# CONTROL_BOARD_V2.net
KiCad netlist of a schematic drawn in Altium Designer
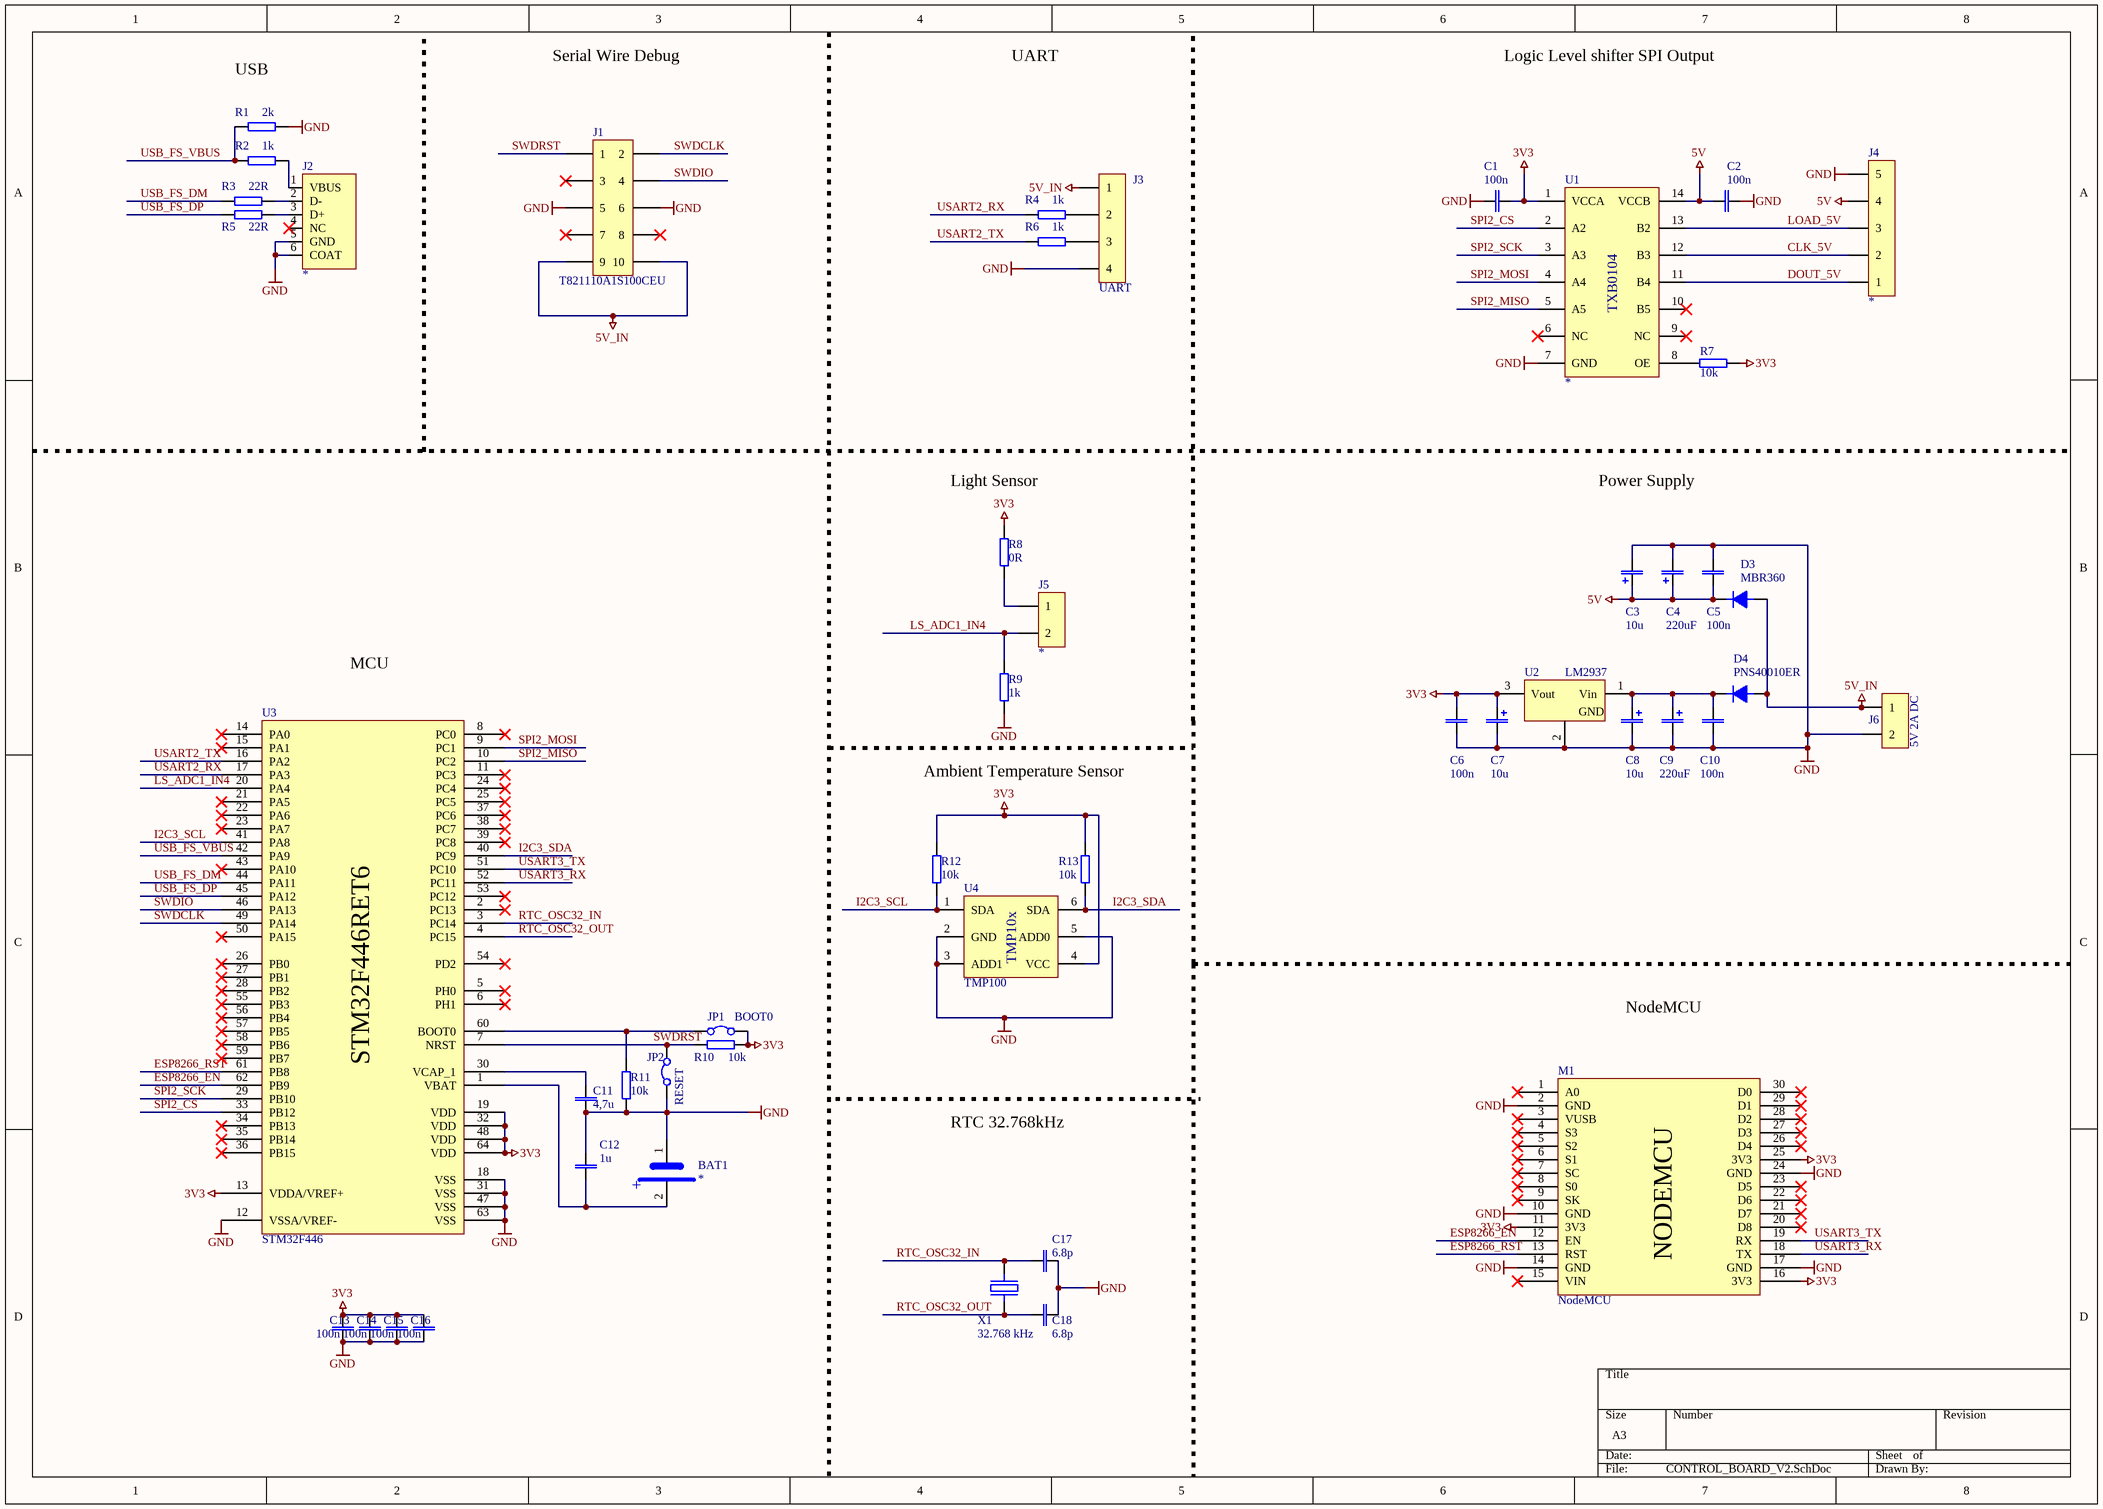
[diagram p0: CONTROL_BOARD_V2.SchDoc]

(export (version "E")
  (design (tool "Eeschema 10.0.6"))
  (components
    (comp (ref "BAT1")
      (value "*")
      (footprint "CR2032")
      (description "battery")
      (libsource (lib "SCH_LIB") (part "Battery"))
    )
    (comp (ref "C1")
      (value "100n")
      (footprint "CAP 0805")
      (description "NON POLARIZED CAPACITOR")
      (libsource (lib "SCH_LIB") (part "CAP"))
    )
    (comp (ref "C2")
      (value "100n")
      (footprint "CAP 0805")
      (description "NON POLARIZED CAPACITOR")
      (libsource (lib "SCH_LIB") (part "CAP"))
    )
    (comp (ref "C3")
      (value "10u")
      (footprint "CAP 1210")
      (description "POLARIZED CAPACITOR")
      (libsource (lib "SCH_LIB") (part "CAP_POL"))
    )
    (comp (ref "C4")
      (value "220uF")
      (footprint "G ELKO")
      (description "POLARIZED CAPACITOR")
      (libsource (lib "SCH_LIB") (part "CAP_POL"))
    )
    (comp (ref "C5")
      (value "100n")
      (footprint "CAP 0805")
      (description "NON POLARIZED CAPACITOR")
      (libsource (lib "SCH_LIB") (part "CAP"))
    )
    (comp (ref "C6")
      (value "100n")
      (footprint "CAP 0805")
      (description "NON POLARIZED CAPACITOR")
      (libsource (lib "SCH_LIB") (part "CAP"))
    )
    (comp (ref "C7")
      (value "10u")
      (footprint "CAP 1210")
      (description "POLARIZED CAPACITOR")
      (libsource (lib "SCH_LIB") (part "CAP_POL"))
    )
    (comp (ref "C8")
      (value "10u")
      (footprint "CAP 1210")
      (description "POLARIZED CAPACITOR")
      (libsource (lib "SCH_LIB") (part "CAP_POL"))
    )
    (comp (ref "C9")
      (value "220uF")
      (footprint "G ELKO")
      (description "POLARIZED CAPACITOR")
      (libsource (lib "SCH_LIB") (part "CAP_POL"))
    )
    (comp (ref "C10")
      (value "100n")
      (footprint "CAP 0805")
      (description "NON POLARIZED CAPACITOR")
      (libsource (lib "SCH_LIB") (part "CAP"))
    )
    (comp (ref "C11")
      (value "4,7u")
      (footprint "CAP 0805")
      (description "NON POLARIZED CAPACITOR")
      (libsource (lib "SCH_LIB") (part "CAP"))
    )
    (comp (ref "C12")
      (value "1u")
      (footprint "CAP 0805")
      (description "NON POLARIZED CAPACITOR")
      (libsource (lib "SCH_LIB") (part "CAP"))
    )
    (comp (ref "C13")
      (value "100n")
      (footprint "CAP 0805")
      (description "NON POLARIZED CAPACITOR")
      (libsource (lib "SCH_LIB") (part "CAP"))
    )
    (comp (ref "C14")
      (value "100n")
      (footprint "CAP 0805")
      (description "NON POLARIZED CAPACITOR")
      (libsource (lib "SCH_LIB") (part "CAP"))
    )
    (comp (ref "C15")
      (value "100n")
      (footprint "CAP 0805")
      (description "NON POLARIZED CAPACITOR")
      (libsource (lib "SCH_LIB") (part "CAP"))
    )
    (comp (ref "C16")
      (value "100n")
      (footprint "CAP 0805")
      (description "NON POLARIZED CAPACITOR")
      (libsource (lib "SCH_LIB") (part "CAP"))
    )
    (comp (ref "C17")
      (value "6.8p")
      (footprint "CAP 0805")
      (description "NON POLARIZED CAPACITOR")
      (libsource (lib "SCH_LIB") (part "CAP"))
    )
    (comp (ref "C18")
      (value "6.8p")
      (footprint "CAP 0805")
      (description "NON POLARIZED CAPACITOR")
      (libsource (lib "SCH_LIB") (part "CAP"))
    )
    (comp (ref "D3")
      (value "MBR360")
      (footprint "DO-201AD")
      (description "ON Semiconductor MBR360,SCHOTTKY BARRIER RECTIFIERS\r\n3.0 AMPERES 60 VOLTS")
      (fields (field (name "MANUFACTURER") "ON Semiconductor"))
      (libsource (lib "SCH_LIB") (part "MBR360"))
    )
    (comp (ref "D4")
      (value "PNS40010ER")
      (footprint "SOD-123")
      (description "Nexperia PNS40010ER,115 switching diode 1.4A, 400V, SOD-123")
      (fields (field (name "MANUFACTURER") "Nexperia"))
      (libsource (lib "SCH_LIB") (part "PNS40010ER"))
    )
    (comp (ref "J1")
      (value "T821110A1S100CEU")
      (footprint "MLW10")
      (description "T821, 10pin, 2x5 connector, 2.54mm")
      (fields (field (name "MANUFACTURER") "Amphenol"))
      (libsource (lib "SCH_LIB") (part "T821-10"))
    )
    (comp (ref "J2")
      (value "*")
      (footprint "MUSB-B2.0S05PFHSB-T")
      (description "5PIN miniUSB SMD connector")
      (libsource (lib "SCH_LIB") (part "USB_5PIN"))
    )
    (comp (ref "J3")
      (value "UART")
      (footprint "SIL4")
      (description "4 PIN HEADER")
      (libsource (lib "SCH_LIB") (part "HEADER4"))
    )
    (comp (ref "J4")
      (value "*")
      (footprint "SIL5")
      (description "5 PIN HEADER")
      (libsource (lib "SCH_LIB") (part "HEADER5"))
    )
    (comp (ref "J5")
      (value "*")
      (footprint "SIL2")
      (description "2 PIN HEADER")
      (libsource (lib "SCH_LIB") (part "HEADER2"))
    )
    (comp (ref "J6")
      (value "5V 2A DC")
      (footprint "PTR_AKZ350")
      (description "2 Pin Terminal Block")
      (fields (field (name "MANUFACTURER") "TE Connectivity"))
      (libsource (lib "SCH_LIB") (part "TB-2"))
    )
    (comp (ref "JP1")
      (value "BOOT0")
      (footprint "SIL2")
      (description "JUMPER")
      (libsource (lib "SCH_LIB") (part "JUMPER"))
    )
    (comp (ref "JP2")
      (value "RESET")
      (footprint "SIL2")
      (description "JUMPER")
      (libsource (lib "SCH_LIB") (part "JUMPER"))
    )
    (comp (ref "M1")
      (value "NodeMCU")
      (footprint "NodeMcu")
      (description "Node MCU ESP12 module")
      (libsource (lib "SCH_LIB") (part "NodeMCU"))
    )
    (comp (ref "R1")
      (value "2k")
      (footprint "RES 0805")
      (description "RESISTOR")
      (libsource (lib "SCH_LIB") (part "RES"))
    )
    (comp (ref "R2")
      (value "1k")
      (footprint "RES 0805")
      (description "RESISTOR")
      (libsource (lib "SCH_LIB") (part "RES"))
    )
    (comp (ref "R3")
      (value "22R")
      (footprint "RES 0805")
      (description "RESISTOR")
      (libsource (lib "SCH_LIB") (part "RES"))
    )
    (comp (ref "R4")
      (value "1k")
      (footprint "RES 0805")
      (description "RESISTOR")
      (libsource (lib "SCH_LIB") (part "RES"))
    )
    (comp (ref "R5")
      (value "22R")
      (footprint "RES 0805")
      (description "RESISTOR")
      (libsource (lib "SCH_LIB") (part "RES"))
    )
    (comp (ref "R6")
      (value "1k")
      (footprint "RES 0805")
      (description "RESISTOR")
      (libsource (lib "SCH_LIB") (part "RES"))
    )
    (comp (ref "R7")
      (value "10k")
      (footprint "RES 0805")
      (description "RESISTOR")
      (libsource (lib "SCH_LIB") (part "RES"))
    )
    (comp (ref "R8")
      (value "0R")
      (footprint "RES 0805")
      (description "RESISTOR")
      (libsource (lib "") (part "RES_2"))
    )
    (comp (ref "R9")
      (value "1k")
      (footprint "RES 0805")
      (description "RESISTOR")
      (libsource (lib "") (part "RES_2"))
    )
    (comp (ref "R10")
      (value "10k")
      (footprint "RES 0805")
      (description "RESISTOR")
      (libsource (lib "") (part "RES_3"))
    )
    (comp (ref "R11")
      (value "10k")
      (footprint "RES 0805")
      (description "RESISTOR")
      (libsource (lib "") (part "RES_1"))
    )
    (comp (ref "R12")
      (value "10k")
      (footprint "RES 0805")
      (description "RESISTOR")
      (libsource (lib "") (part "RES_1"))
    )
    (comp (ref "R13")
      (value "10k")
      (footprint "RES 0805")
      (description "RESISTOR")
      (libsource (lib "") (part "RES_1"))
    )
    (comp (ref "U1")
      (value "*")
      (footprint "SO14")
      (description "Voltage level shifter")
      (libsource (lib "SCH_LIB") (part "TXB0104"))
    )
    (comp (ref "U2")
      (value "LM2937")
      (footprint "SOT223")
      (description "LDO-regulator 400mA 3,3 V 5%, 4,75 → 26 V, SOT223")
      (fields (field (name "MANUFACTURER") "Texas Instruments"))
      (libsource (lib "SCH_LIB") (part "LM2937"))
    )
    (comp (ref "U3")
      (value "STM32F446")
      (footprint "LQFP64")
      (description "MCU STM32F446RET6 32bit, ARM Cortex M4, 180MHz, Flash, 128 kB RAM, 2xUSB USB, LQFP-64")
      (fields (field (name "MANUFACTURER") "ST Microelectronics"))
      (libsource (lib "SCH_LIB") (part "STM32F446RET6"))
    )
    (comp (ref "U4")
      (value "TMP100")
      (footprint "SOT-23-6L")
      (description "Temperature sensor with I2C interface")
      (fields (field (name "MANUFACTURER") "Texas Instruments"))
      (libsource (lib "SCH_LIB") (part "TMP10x"))
    )
    (comp (ref "X1")
      (value "32.768 kHz")
      (footprint "X32K768L104")
      (description "Crystal, 32.768 kHz, Cylinder Radial, 8mm x 3mm Dia, 12.5 pF, 20 ppm")
      (fields (field (name "MANUFACTURER") "AEL CRYSTALS"))
      (libsource (lib "SCH_LIB") (part "X32K768L104"))
    )
  )
  (nets
    (net (code "1") (name "/CLK_5V") (class "Default")
      (node (ref "J4") (pin "2") (pinfunction "2_2") (pintype "passive"))
      (node (ref "U1") (pin "12") (pinfunction "B3_12") (pintype "passive"))
    )
    (net (code "2") (name "/DOUT_5V") (class "Default")
      (node (ref "J4") (pin "1") (pinfunction "1_1") (pintype "passive"))
      (node (ref "U1") (pin "11") (pinfunction "B4_11") (pintype "passive"))
    )
    (net (code "3") (name "/ESP8266_EN") (class "Default")
      (node (ref "M1") (pin "12") (pinfunction "EN_12") (pintype "passive"))
      (node (ref "U3") (pin "62") (pinfunction "PB9_62") (pintype "passive"))
    )
    (net (code "4") (name "/ESP8266_RST") (class "Default")
      (node (ref "M1") (pin "13") (pinfunction "RST_13") (pintype "passive"))
      (node (ref "U3") (pin "61") (pinfunction "PB8_61") (pintype "passive"))
    )
    (net (code "5") (name "/I2C3_SCL") (class "Default")
      (node (ref "R12") (pin "1") (pinfunction "1_1") (pintype "passive"))
      (node (ref "U3") (pin "41") (pinfunction "PA8_41") (pintype "passive"))
      (node (ref "U4") (pin "1") (pinfunction "SDA_1") (pintype "passive"))
    )
    (net (code "6") (name "/I2C3_SDA") (class "Default")
      (node (ref "R13") (pin "1") (pinfunction "1_1") (pintype "passive"))
      (node (ref "U3") (pin "40") (pinfunction "PC9_40") (pintype "passive"))
      (node (ref "U4") (pin "6") (pinfunction "SDA_6") (pintype "passive"))
    )
    (net (code "7") (name "/LOAD_5V") (class "Default")
      (node (ref "J4") (pin "3") (pinfunction "3_3") (pintype "passive"))
      (node (ref "U1") (pin "13") (pinfunction "B2_13") (pintype "passive"))
    )
    (net (code "8") (name "/LS_ADC1_IN4") (class "Default")
      (node (ref "J5") (pin "2") (pinfunction "2_2") (pintype "passive"))
      (node (ref "R9") (pin "1") (pinfunction "1_1") (pintype "passive"))
      (node (ref "U3") (pin "20") (pinfunction "PA4_20") (pintype "passive"))
    )
    (net (code "9") (name "/RTC_OSC32_IN") (class "Default")
      (node (ref "C17") (pin "2") (pinfunction "2_2") (pintype "passive"))
      (node (ref "U3") (pin "3") (pinfunction "PC14_3") (pintype "passive"))
      (node (ref "X1") (pin "2") (pinfunction "GND_2") (pintype "passive"))
    )
    (net (code "10") (name "/RTC_OSC32_OUT") (class "Default")
      (node (ref "C18") (pin "2") (pinfunction "2_2") (pintype "passive"))
      (node (ref "U3") (pin "4") (pinfunction "PC15_4") (pintype "passive"))
      (node (ref "X1") (pin "1") (pinfunction "1_1") (pintype "passive"))
    )
    (net (code "11") (name "/SPI2_CS") (class "Default")
      (node (ref "U1") (pin "2") (pinfunction "A2_2") (pintype "passive"))
      (node (ref "U3") (pin "33") (pinfunction "PB12_33") (pintype "passive"))
    )
    (net (code "12") (name "/SPI2_MISO") (class "Default")
      (node (ref "U1") (pin "5") (pinfunction "A5_5") (pintype "passive"))
      (node (ref "U3") (pin "10") (pinfunction "PC2_10") (pintype "passive"))
    )
    (net (code "13") (name "/SPI2_MOSI") (class "Default")
      (node (ref "U1") (pin "4") (pinfunction "A4_4") (pintype "passive"))
      (node (ref "U3") (pin "9") (pinfunction "PC1_9") (pintype "passive"))
    )
    (net (code "14") (name "/SPI2_SCK") (class "Default")
      (node (ref "U1") (pin "3") (pinfunction "A3_3") (pintype "passive"))
      (node (ref "U3") (pin "29") (pinfunction "PB10_29") (pintype "passive"))
    )
    (net (code "15") (name "/SWDCLK") (class "Default")
      (node (ref "J1") (pin "2") (pinfunction "2_2") (pintype "passive"))
      (node (ref "U3") (pin "49") (pinfunction "PA14_49") (pintype "passive"))
    )
    (net (code "16") (name "/SWDIO") (class "Default")
      (node (ref "J1") (pin "4") (pinfunction "4_4") (pintype "passive"))
      (node (ref "U3") (pin "46") (pinfunction "PA13_46") (pintype "passive"))
    )
    (net (code "17") (name "/SWDRST") (class "Default")
      (node (ref "J1") (pin "1") (pinfunction "1_1") (pintype "passive"))
      (node (ref "JP2") (pin "2") (pinfunction "2_2") (pintype "passive"))
      (node (ref "R10") (pin "1") (pinfunction "1_1") (pintype "passive"))
      (node (ref "U3") (pin "7") (pinfunction "NRST_7") (pintype "passive"))
    )
    (net (code "18") (name "/USART2_RX") (class "Default")
      (node (ref "R4") (pin "2") (pinfunction "2_2") (pintype "passive"))
      (node (ref "U3") (pin "17") (pinfunction "PA3_17") (pintype "passive"))
    )
    (net (code "19") (name "/USART2_TX") (class "Default")
      (node (ref "R6") (pin "2") (pinfunction "2_2") (pintype "passive"))
      (node (ref "U3") (pin "16") (pinfunction "PA2_16") (pintype "passive"))
    )
    (net (code "20") (name "/USART3_RX") (class "Default")
      (node (ref "M1") (pin "18") (pinfunction "TX_18") (pintype "passive"))
      (node (ref "U3") (pin "52") (pinfunction "PC11_52") (pintype "passive"))
    )
    (net (code "21") (name "/USART3_TX") (class "Default")
      (node (ref "M1") (pin "19") (pinfunction "RX_19") (pintype "passive"))
      (node (ref "U3") (pin "51") (pinfunction "PC10_51") (pintype "passive"))
    )
    (net (code "22") (name "/USB_FS_DM") (class "Default")
      (node (ref "R3") (pin "2") (pinfunction "2_2") (pintype "passive"))
      (node (ref "U3") (pin "44") (pinfunction "PA11_44") (pintype "passive"))
    )
    (net (code "23") (name "/USB_FS_DP") (class "Default")
      (node (ref "R5") (pin "2") (pinfunction "2_2") (pintype "passive"))
      (node (ref "U3") (pin "45") (pinfunction "PA12_45") (pintype "passive"))
    )
    (net (code "24") (name "/USB_FS_VBUS") (class "Default")
      (node (ref "R1") (pin "2") (pinfunction "2_2") (pintype "passive"))
      (node (ref "R2") (pin "2") (pinfunction "2_2") (pintype "passive"))
      (node (ref "U3") (pin "42") (pinfunction "PA9_42") (pintype "passive"))
    )
    (net (code "25") (name "3V3") (class "Default")
      (node (ref "C1") (pin "2") (pinfunction "2_2") (pintype "passive"))
      (node (ref "C13") (pin "2") (pinfunction "2_2") (pintype "passive"))
      (node (ref "C14") (pin "2") (pinfunction "2_2") (pintype "passive"))
      (node (ref "C15") (pin "2") (pinfunction "2_2") (pintype "passive"))
      (node (ref "C16") (pin "2") (pinfunction "2_2") (pintype "passive"))
      (node (ref "C6") (pin "1") (pinfunction "1_1") (pintype "passive"))
      (node (ref "C7") (pin "1") (pinfunction "+_1") (pintype "passive"))
      (node (ref "JP1") (pin "2") (pinfunction "2_2") (pintype "passive"))
      (node (ref "M1") (pin "11") (pinfunction "3V3_11") (pintype "passive"))
      (node (ref "M1") (pin "16") (pinfunction "3V3_16") (pintype "passive"))
      (node (ref "M1") (pin "25") (pinfunction "3V3_25") (pintype "passive"))
      (node (ref "R10") (pin "2") (pinfunction "2_2") (pintype "passive"))
      (node (ref "R12") (pin "2") (pinfunction "2_2") (pintype "passive"))
      (node (ref "R13") (pin "2") (pinfunction "2_2") (pintype "passive"))
      (node (ref "R7") (pin "1") (pinfunction "1_1") (pintype "passive"))
      (node (ref "R8") (pin "1") (pinfunction "1_1") (pintype "passive"))
      (node (ref "U1") (pin "1") (pinfunction "VCCA_1") (pintype "passive"))
      (node (ref "U2") (pin "3") (pinfunction "Vout_3") (pintype "passive"))
      (node (ref "U3") (pin "13") (pinfunction "VDDA/VREF+_13") (pintype "passive"))
      (node (ref "U3") (pin "19") (pinfunction "VDD_19") (pintype "passive"))
      (node (ref "U3") (pin "32") (pinfunction "VDD_32") (pintype "passive"))
      (node (ref "U3") (pin "48") (pinfunction "VDD_48") (pintype "passive"))
      (node (ref "U3") (pin "64") (pinfunction "VDD_64") (pintype "passive"))
      (node (ref "U4") (pin "4") (pinfunction "VCC_4") (pintype "passive"))
    )
    (net (code "26") (name "5V") (class "Default")
      (node (ref "C2") (pin "1") (pinfunction "1_1") (pintype "passive"))
      (node (ref "C3") (pin "1") (pinfunction "+_1") (pintype "passive"))
      (node (ref "C4") (pin "1") (pinfunction "+_1") (pintype "passive"))
      (node (ref "C5") (pin "2") (pinfunction "2_2") (pintype "passive"))
      (node (ref "D3") (pin "2") (pinfunction "K_2") (pintype "passive"))
      (node (ref "J4") (pin "4") (pinfunction "4_4") (pintype "passive"))
      (node (ref "U1") (pin "14") (pinfunction "VCCB_14") (pintype "passive"))
    )
    (net (code "27") (name "5V_IN") (class "Default")
      (node (ref "D3") (pin "1") (pinfunction "A_1") (pintype "passive"))
      (node (ref "D4") (pin "1") (pinfunction "A_1") (pintype "passive"))
      (node (ref "J1") (pin "10") (pinfunction "10_10") (pintype "passive"))
      (node (ref "J1") (pin "9") (pinfunction "9_9") (pintype "passive"))
      (node (ref "J3") (pin "1") (pinfunction "1_1") (pintype "passive"))
      (node (ref "J6") (pin "1") (pinfunction "1_1") (pintype "passive"))
    )
    (net (code "28") (name "GND") (class "Default")
      (node (ref "BAT1") (pin "1") (pintype "passive"))
      (node (ref "C1") (pin "1") (pinfunction "1_1") (pintype "passive"))
      (node (ref "C10") (pin "2") (pinfunction "2_2") (pintype "passive"))
      (node (ref "C11") (pin "1") (pinfunction "1_1") (pintype "passive"))
      (node (ref "C12") (pin "1") (pinfunction "1_1") (pintype "passive"))
      (node (ref "C13") (pin "1") (pinfunction "1_1") (pintype "passive"))
      (node (ref "C14") (pin "1") (pinfunction "1_1") (pintype "passive"))
      (node (ref "C15") (pin "1") (pinfunction "1_1") (pintype "passive"))
      (node (ref "C16") (pin "1") (pinfunction "1_1") (pintype "passive"))
      (node (ref "C17") (pin "1") (pinfunction "1_1") (pintype "passive"))
      (node (ref "C18") (pin "1") (pinfunction "1_1") (pintype "passive"))
      (node (ref "C2") (pin "2") (pinfunction "2_2") (pintype "passive"))
      (node (ref "C3") (pin "2") (pinfunction "-_2") (pintype "passive"))
      (node (ref "C4") (pin "2") (pinfunction "-_2") (pintype "passive"))
      (node (ref "C5") (pin "1") (pinfunction "1_1") (pintype "passive"))
      (node (ref "C6") (pin "2") (pinfunction "2_2") (pintype "passive"))
      (node (ref "C7") (pin "2") (pinfunction "-_2") (pintype "passive"))
      (node (ref "C8") (pin "2") (pinfunction "-_2") (pintype "passive"))
      (node (ref "C9") (pin "2") (pinfunction "-_2") (pintype "passive"))
      (node (ref "J1") (pin "5") (pinfunction "5_5") (pintype "passive"))
      (node (ref "J1") (pin "6") (pinfunction "6_6") (pintype "passive"))
      (node (ref "J2") (pin "5") (pinfunction "GND_5") (pintype "passive"))
      (node (ref "J2") (pin "6") (pinfunction "COAT_6") (pintype "passive"))
      (node (ref "J3") (pin "4") (pinfunction "4_4") (pintype "passive"))
      (node (ref "J4") (pin "5") (pinfunction "5_5") (pintype "passive"))
      (node (ref "J6") (pin "2") (pinfunction "2_2") (pintype "passive"))
      (node (ref "JP2") (pin "1") (pinfunction "1_1") (pintype "passive"))
      (node (ref "M1") (pin "10") (pinfunction "GND_10") (pintype "passive"))
      (node (ref "M1") (pin "14") (pinfunction "GND_14") (pintype "passive"))
      (node (ref "M1") (pin "17") (pinfunction "GND_17") (pintype "passive"))
      (node (ref "M1") (pin "2") (pinfunction "GND_2") (pintype "passive"))
      (node (ref "M1") (pin "24") (pinfunction "GND_24") (pintype "passive"))
      (node (ref "R1") (pin "1") (pinfunction "1_1") (pintype "passive"))
      (node (ref "R11") (pin "1") (pinfunction "1_1") (pintype "passive"))
      (node (ref "R9") (pin "2") (pinfunction "2_2") (pintype "passive"))
      (node (ref "U1") (pin "7") (pinfunction "GND_7") (pintype "passive"))
      (node (ref "U2") (pin "2") (pinfunction "GND_2") (pintype "passive"))
      (node (ref "U3") (pin "12") (pinfunction "VSSA/VREF-_12") (pintype "passive"))
      (node (ref "U3") (pin "18") (pinfunction "VSS_18") (pintype "passive"))
      (node (ref "U3") (pin "31") (pinfunction "VSS_31") (pintype "passive"))
      (node (ref "U3") (pin "47") (pinfunction "VSS_47") (pintype "passive"))
      (node (ref "U3") (pin "63") (pinfunction "VSS_63") (pintype "passive"))
      (node (ref "U4") (pin "2") (pinfunction "GND_2") (pintype "passive"))
      (node (ref "U4") (pin "3") (pinfunction "ADD1_3") (pintype "passive"))
      (node (ref "U4") (pin "5") (pinfunction "ADD0_5") (pintype "passive"))
    )
    (net (code "29") (name "Net-(C8-+)") (class "Default")
      (node (ref "C10") (pin "1") (pinfunction "1_1") (pintype "passive"))
      (node (ref "C8") (pin "1") (pinfunction "+_1") (pintype "passive"))
      (node (ref "C9") (pin "1") (pinfunction "+_1") (pintype "passive"))
      (node (ref "D4") (pin "2") (pinfunction "K_2") (pintype "passive"))
      (node (ref "U2") (pin "1") (pinfunction "Vin_1") (pintype "passive"))
    )
    (net (code "30") (name "Net-(J2-D+)") (class "Default")
      (node (ref "J2") (pin "3") (pinfunction "D+_3") (pintype "passive"))
      (node (ref "R5") (pin "1") (pinfunction "1_1") (pintype "passive"))
    )
    (net (code "31") (name "Net-(J2-D-)") (class "Default")
      (node (ref "J2") (pin "2") (pinfunction "D-_2") (pintype "passive"))
      (node (ref "R3") (pin "1") (pinfunction "1_1") (pintype "passive"))
    )
    (net (code "32") (name "Net-(J2-VBUS)") (class "Default")
      (node (ref "J2") (pin "1") (pinfunction "VBUS_1") (pintype "passive"))
      (node (ref "R2") (pin "1") (pinfunction "1_1") (pintype "passive"))
    )
    (net (code "33") (name "Net-(J3-Pad2)") (class "Default")
      (node (ref "J3") (pin "2") (pinfunction "2_2") (pintype "passive"))
      (node (ref "R4") (pin "1") (pinfunction "1_1") (pintype "passive"))
    )
    (net (code "34") (name "Net-(J3-Pad3)") (class "Default")
      (node (ref "J3") (pin "3") (pinfunction "3_3") (pintype "passive"))
      (node (ref "R6") (pin "1") (pinfunction "1_1") (pintype "passive"))
    )
    (net (code "35") (name "Net-(J5-Pad1)") (class "Default")
      (node (ref "J5") (pin "1") (pinfunction "1_1") (pintype "passive"))
      (node (ref "R8") (pin "2") (pinfunction "2_2") (pintype "passive"))
    )
    (net (code "36") (name "Net-(U1-OE)") (class "Default")
      (node (ref "R7") (pin "2") (pinfunction "2_2") (pintype "passive"))
      (node (ref "U1") (pin "8") (pinfunction "OE_8") (pintype "passive"))
    )
    (net (code "37") (name "Net-(U3-BOOT0)") (class "Default")
      (node (ref "JP1") (pin "1") (pinfunction "1_1") (pintype "passive"))
      (node (ref "R11") (pin "2") (pinfunction "2_2") (pintype "passive"))
      (node (ref "U3") (pin "60") (pinfunction "BOOT0_60") (pintype "passive"))
    )
    (net (code "38") (name "Net-(U3-VBAT)") (class "Default")
      (node (ref "BAT1") (pin "2") (pintype "passive"))
      (node (ref "C12") (pin "2") (pinfunction "2_2") (pintype "passive"))
      (node (ref "U3") (pin "1") (pinfunction "VBAT_1") (pintype "passive"))
    )
    (net (code "39") (name "Net-(U3-VCAP_1)") (class "Default")
      (node (ref "C11") (pin "2") (pinfunction "2_2") (pintype "passive"))
      (node (ref "U3") (pin "30") (pinfunction "VCAP_1_30") (pintype "passive"))
    )
    (net (code "40") (name "unconnected-(J1-Pad3)") (class "Default")
      (node (ref "J1") (pin "3") (pinfunction "3_3") (pintype "passive+no_connect"))
    )
    (net (code "41") (name "unconnected-(J1-Pad7)") (class "Default")
      (node (ref "J1") (pin "7") (pinfunction "7_7") (pintype "passive+no_connect"))
    )
    (net (code "42") (name "unconnected-(J1-Pad8)") (class "Default")
      (node (ref "J1") (pin "8") (pinfunction "8_8") (pintype "passive+no_connect"))
    )
    (net (code "43") (name "unconnected-(J2-NC-Pad4)") (class "Default")
      (node (ref "J2") (pin "4") (pinfunction "NC_4") (pintype "passive+no_connect"))
    )
    (net (code "44") (name "unconnected-(M1-A0-Pad1)") (class "Default")
      (node (ref "M1") (pin "1") (pinfunction "A0_1") (pintype "passive+no_connect"))
    )
    (net (code "45") (name "unconnected-(M1-D0-Pad30)") (class "Default")
      (node (ref "M1") (pin "30") (pinfunction "D0_30") (pintype "passive+no_connect"))
    )
    (net (code "46") (name "unconnected-(M1-D1-Pad29)") (class "Default")
      (node (ref "M1") (pin "29") (pinfunction "D1_29") (pintype "passive+no_connect"))
    )
    (net (code "47") (name "unconnected-(M1-D2-Pad28)") (class "Default")
      (node (ref "M1") (pin "28") (pinfunction "D2_28") (pintype "passive+no_connect"))
    )
    (net (code "48") (name "unconnected-(M1-D3-Pad27)") (class "Default")
      (node (ref "M1") (pin "27") (pinfunction "D3_27") (pintype "passive+no_connect"))
    )
    (net (code "49") (name "unconnected-(M1-D4-Pad26)") (class "Default")
      (node (ref "M1") (pin "26") (pinfunction "D4_26") (pintype "passive+no_connect"))
    )
    (net (code "50") (name "unconnected-(M1-D5-Pad23)") (class "Default")
      (node (ref "M1") (pin "23") (pinfunction "D5_23") (pintype "passive+no_connect"))
    )
    (net (code "51") (name "unconnected-(M1-D6-Pad22)") (class "Default")
      (node (ref "M1") (pin "22") (pinfunction "D6_22") (pintype "passive+no_connect"))
    )
    (net (code "52") (name "unconnected-(M1-D7-Pad21)") (class "Default")
      (node (ref "M1") (pin "21") (pinfunction "D7_21") (pintype "passive+no_connect"))
    )
    (net (code "53") (name "unconnected-(M1-D8-Pad20)") (class "Default")
      (node (ref "M1") (pin "20") (pinfunction "D8_20") (pintype "passive+no_connect"))
    )
    (net (code "54") (name "unconnected-(M1-S0-Pad8)") (class "Default")
      (node (ref "M1") (pin "8") (pinfunction "S0_8") (pintype "passive+no_connect"))
    )
    (net (code "55") (name "unconnected-(M1-S1-Pad6)") (class "Default")
      (node (ref "M1") (pin "6") (pinfunction "S1_6") (pintype "passive+no_connect"))
    )
    (net (code "56") (name "unconnected-(M1-S2-Pad5)") (class "Default")
      (node (ref "M1") (pin "5") (pinfunction "S2_5") (pintype "passive+no_connect"))
    )
    (net (code "57") (name "unconnected-(M1-S3-Pad4)") (class "Default")
      (node (ref "M1") (pin "4") (pinfunction "S3_4") (pintype "passive+no_connect"))
    )
    (net (code "58") (name "unconnected-(M1-SC-Pad7)") (class "Default")
      (node (ref "M1") (pin "7") (pinfunction "SC_7") (pintype "passive+no_connect"))
    )
    (net (code "59") (name "unconnected-(M1-SK-Pad9)") (class "Default")
      (node (ref "M1") (pin "9") (pinfunction "SK_9") (pintype "passive+no_connect"))
    )
    (net (code "60") (name "unconnected-(M1-VIN-Pad15)") (class "Default")
      (node (ref "M1") (pin "15") (pinfunction "VIN_15") (pintype "passive+no_connect"))
    )
    (net (code "61") (name "unconnected-(M1-VUSB-Pad3)") (class "Default")
      (node (ref "M1") (pin "3") (pinfunction "VUSB_3") (pintype "passive+no_connect"))
    )
    (net (code "62") (name "unconnected-(U1-B5-Pad10)") (class "Default")
      (node (ref "U1") (pin "10") (pinfunction "B5_10") (pintype "passive+no_connect"))
    )
    (net (code "63") (name "unconnected-(U1-NC-Pad6)") (class "Default")
      (node (ref "U1") (pin "6") (pinfunction "NC_6") (pintype "passive+no_connect"))
    )
    (net (code "64") (name "unconnected-(U1-NC-Pad9)") (class "Default")
      (node (ref "U1") (pin "9") (pinfunction "NC_9") (pintype "passive+no_connect"))
    )
    (net (code "65") (name "unconnected-(U3-PA0-Pad14)") (class "Default")
      (node (ref "U3") (pin "14") (pinfunction "PA0_14") (pintype "passive+no_connect"))
    )
    (net (code "66") (name "unconnected-(U3-PA1-Pad15)") (class "Default")
      (node (ref "U3") (pin "15") (pinfunction "PA1_15") (pintype "passive+no_connect"))
    )
    (net (code "67") (name "unconnected-(U3-PA5-Pad21)") (class "Default")
      (node (ref "U3") (pin "21") (pinfunction "PA5_21") (pintype "passive+no_connect"))
    )
    (net (code "68") (name "unconnected-(U3-PA6-Pad22)") (class "Default")
      (node (ref "U3") (pin "22") (pinfunction "PA6_22") (pintype "passive+no_connect"))
    )
    (net (code "69") (name "unconnected-(U3-PA7-Pad23)") (class "Default")
      (node (ref "U3") (pin "23") (pinfunction "PA7_23") (pintype "passive+no_connect"))
    )
    (net (code "70") (name "unconnected-(U3-PA10-Pad43)") (class "Default")
      (node (ref "U3") (pin "43") (pinfunction "PA10_43") (pintype "passive+no_connect"))
    )
    (net (code "71") (name "unconnected-(U3-PA15-Pad50)") (class "Default")
      (node (ref "U3") (pin "50") (pinfunction "PA15_50") (pintype "passive+no_connect"))
    )
    (net (code "72") (name "unconnected-(U3-PB0-Pad26)") (class "Default")
      (node (ref "U3") (pin "26") (pinfunction "PB0_26") (pintype "passive+no_connect"))
    )
    (net (code "73") (name "unconnected-(U3-PB1-Pad27)") (class "Default")
      (node (ref "U3") (pin "27") (pinfunction "PB1_27") (pintype "passive+no_connect"))
    )
    (net (code "74") (name "unconnected-(U3-PB2-Pad28)") (class "Default")
      (node (ref "U3") (pin "28") (pinfunction "PB2_28") (pintype "passive+no_connect"))
    )
    (net (code "75") (name "unconnected-(U3-PB3-Pad55)") (class "Default")
      (node (ref "U3") (pin "55") (pinfunction "PB3_55") (pintype "passive+no_connect"))
    )
    (net (code "76") (name "unconnected-(U3-PB4-Pad56)") (class "Default")
      (node (ref "U3") (pin "56") (pinfunction "PB4_56") (pintype "passive+no_connect"))
    )
    (net (code "77") (name "unconnected-(U3-PB5-Pad57)") (class "Default")
      (node (ref "U3") (pin "57") (pinfunction "PB5_57") (pintype "passive+no_connect"))
    )
    (net (code "78") (name "unconnected-(U3-PB6-Pad58)") (class "Default")
      (node (ref "U3") (pin "58") (pinfunction "PB6_58") (pintype "passive+no_connect"))
    )
    (net (code "79") (name "unconnected-(U3-PB7-Pad59)") (class "Default")
      (node (ref "U3") (pin "59") (pinfunction "PB7_59") (pintype "passive+no_connect"))
    )
    (net (code "80") (name "unconnected-(U3-PB13-Pad34)") (class "Default")
      (node (ref "U3") (pin "34") (pinfunction "PB13_34") (pintype "passive+no_connect"))
    )
    (net (code "81") (name "unconnected-(U3-PB14-Pad35)") (class "Default")
      (node (ref "U3") (pin "35") (pinfunction "PB14_35") (pintype "passive+no_connect"))
    )
    (net (code "82") (name "unconnected-(U3-PB15-Pad36)") (class "Default")
      (node (ref "U3") (pin "36") (pinfunction "PB15_36") (pintype "passive+no_connect"))
    )
    (net (code "83") (name "unconnected-(U3-PC0-Pad8)") (class "Default")
      (node (ref "U3") (pin "8") (pinfunction "PC0_8") (pintype "passive+no_connect"))
    )
    (net (code "84") (name "unconnected-(U3-PC3-Pad11)") (class "Default")
      (node (ref "U3") (pin "11") (pinfunction "PC3_11") (pintype "passive+no_connect"))
    )
    (net (code "85") (name "unconnected-(U3-PC4-Pad24)") (class "Default")
      (node (ref "U3") (pin "24") (pinfunction "PC4_24") (pintype "passive+no_connect"))
    )
    (net (code "86") (name "unconnected-(U3-PC5-Pad25)") (class "Default")
      (node (ref "U3") (pin "25") (pinfunction "PC5_25") (pintype "passive+no_connect"))
    )
    (net (code "87") (name "unconnected-(U3-PC6-Pad37)") (class "Default")
      (node (ref "U3") (pin "37") (pinfunction "PC6_37") (pintype "passive+no_connect"))
    )
    (net (code "88") (name "unconnected-(U3-PC7-Pad38)") (class "Default")
      (node (ref "U3") (pin "38") (pinfunction "PC7_38") (pintype "passive+no_connect"))
    )
    (net (code "89") (name "unconnected-(U3-PC8-Pad39)") (class "Default")
      (node (ref "U3") (pin "39") (pinfunction "PC8_39") (pintype "passive+no_connect"))
    )
    (net (code "90") (name "unconnected-(U3-PC12-Pad53)") (class "Default")
      (node (ref "U3") (pin "53") (pinfunction "PC12_53") (pintype "passive+no_connect"))
    )
    (net (code "91") (name "unconnected-(U3-PC13-Pad2)") (class "Default")
      (node (ref "U3") (pin "2") (pinfunction "PC13_2") (pintype "passive+no_connect"))
    )
    (net (code "92") (name "unconnected-(U3-PD2-Pad54)") (class "Default")
      (node (ref "U3") (pin "54") (pinfunction "PD2_54") (pintype "passive+no_connect"))
    )
    (net (code "93") (name "unconnected-(U3-PH0-Pad5)") (class "Default")
      (node (ref "U3") (pin "5") (pinfunction "PH0_5") (pintype "passive+no_connect"))
    )
    (net (code "94") (name "unconnected-(U3-PH1-Pad6)") (class "Default")
      (node (ref "U3") (pin "6") (pinfunction "PH1_6") (pintype "passive+no_connect"))
    )
  )
)
